# EFR32_IO.net
KiCad netlist of a schematic drawn in Altium Designer
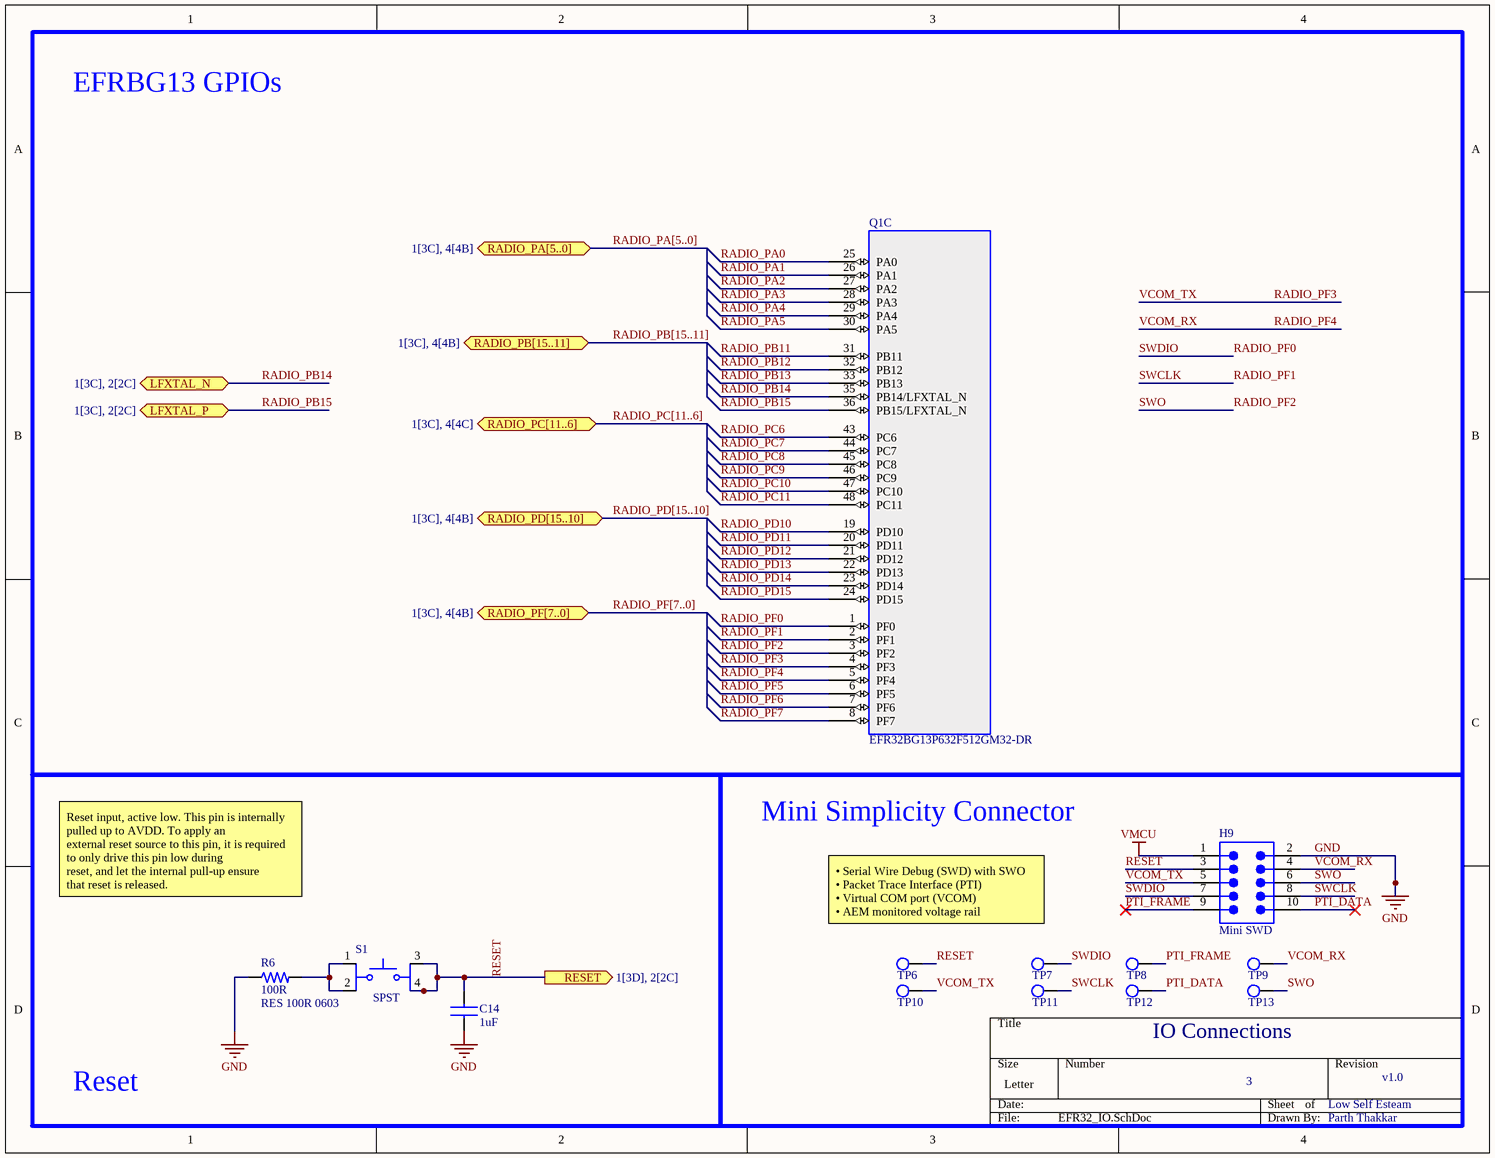
[diagram p0: EFR32_IO.SchDoc]

(export (version "E")
  (design (tool "Eeschema 10.0.6"))
  (components
    (comp (ref "C14")
      (value "1uF")
      (footprint "Capacitor 0603")
      (fields
        (field (name "MANUFACTURER") "Murata")
        (field (name "MANUFACTURER PART NUMBER") "GRM188R61A105KA61D")
        (field (name "Comment") "CAP 1uF 10V 0603")
      )
      (libsource (lib "Keyboard_parts") (part "CAP 1uF 10V 0603"))
    )
    (comp (ref "H9")
      (value "Mini SWD")
      (footprint "Mini Simplicity Connector")
      (description "Mini SWD 0.05\" Pitch Connector - 10 Pin SMT Box Header")
      (fields
        (field (name "MANUFACTURER") "Adafruit Industries")
        (field (name "MANUFACTURER PART NUMBER") "4048")
      )
      (libsource (lib "Keyboard_parts") (part "Debug Connector Mini SWD - 0.05{dblquote}"))
    )
    (comp (ref "Q1")
      (value "EFR32BG13P632F512GM32-DR")
      (footprint "EFR32BG")
      (description "BLue Gecko")
      (fields (field (name "MANUFACTURER") "Silicon Labs"))
      (libsource (lib "Keyboard_parts") (part "EFR32BG13P632F512GM32-DR"))
    )
    (comp (ref "R6")
      (value "RES 100R 0603")
      (footprint "Resistor 0603")
      (fields
        (field (name "MANUFACTURER") "Yageo")
        (field (name "MANUFACTURER PART NUMBER") "RC0603FR-07100RL")
        (field (name "TOLERANCE") "1%")
        (field (name "ALTIUM_VALUE") "100R")
      )
      (libsource (lib "Keyboard_parts") (part "RES 100R 0603"))
    )
    (comp (ref "S1")
      (value "SPST")
      (footprint "SPST")
      (fields
        (field (name "MANUFACTURER") "E-Switch")
        (field (name "MANUFACTURER PART NUMBER") "TL3301NF260QG")
      )
      (libsource (lib "Keyboard_parts") (part "SPST"))
    )
    (comp (ref "TP6")
      (value "Test point")
      (footprint "Test Point")
      (libsource (lib "Keyboard_parts") (part "Test point"))
    )
    (comp (ref "TP7")
      (value "Test point")
      (footprint "Test Point")
      (libsource (lib "Keyboard_parts") (part "Test point"))
    )
    (comp (ref "TP8")
      (value "Test point")
      (footprint "Test Point")
      (libsource (lib "Keyboard_parts") (part "Test point"))
    )
    (comp (ref "TP9")
      (value "Test point")
      (footprint "Test Point")
      (libsource (lib "Keyboard_parts") (part "Test point"))
    )
    (comp (ref "TP10")
      (value "Test point")
      (footprint "Test Point")
      (libsource (lib "Keyboard_parts") (part "Test point"))
    )
    (comp (ref "TP11")
      (value "Test point")
      (footprint "Test Point")
      (libsource (lib "Keyboard_parts") (part "Test point"))
    )
    (comp (ref "TP12")
      (value "Test point")
      (footprint "Test Point")
      (libsource (lib "Keyboard_parts") (part "Test point"))
    )
    (comp (ref "TP13")
      (value "Test point")
      (footprint "Test Point")
      (libsource (lib "Keyboard_parts") (part "Test point"))
    )
  )
  (nets
    (net (code "1") (name "/PTI_DATA") (class "Default")
      (node (ref "H9") (pin "10") (pinfunction "10_10") (pintype "passive"))
      (node (ref "TP12") (pin "1") (pinfunction "1_1") (pintype "passive"))
    )
    (net (code "2") (name "/PTI_FRAME") (class "Default")
      (node (ref "H9") (pin "9") (pinfunction "9_9") (pintype "passive"))
      (node (ref "TP8") (pin "1") (pinfunction "1_1") (pintype "passive"))
    )
    (net (code "3") (name "/RADIO_PA0") (class "Default")
      (node (ref "Q1") (pin "25") (pinfunction "PA0_25") (pintype "bidirectional"))
    )
    (net (code "4") (name "/RADIO_PA1") (class "Default")
      (node (ref "Q1") (pin "26") (pinfunction "PA1_26") (pintype "bidirectional"))
    )
    (net (code "5") (name "/RADIO_PA2") (class "Default")
      (node (ref "Q1") (pin "27") (pinfunction "PA2_27") (pintype "bidirectional"))
    )
    (net (code "6") (name "/RADIO_PA3") (class "Default")
      (node (ref "Q1") (pin "28") (pinfunction "PA3_28") (pintype "bidirectional"))
    )
    (net (code "7") (name "/RADIO_PA4") (class "Default")
      (node (ref "Q1") (pin "29") (pinfunction "PA4_29") (pintype "bidirectional"))
    )
    (net (code "8") (name "/RADIO_PA5") (class "Default")
      (node (ref "Q1") (pin "30") (pinfunction "PA5_30") (pintype "bidirectional"))
    )
    (net (code "10") (name "/RADIO_PB11") (class "Default")
      (node (ref "Q1") (pin "31") (pinfunction "PB11_31") (pintype "bidirectional"))
    )
    (net (code "11") (name "/RADIO_PB12") (class "Default")
      (node (ref "Q1") (pin "32") (pinfunction "PB12_32") (pintype "bidirectional"))
    )
    (net (code "12") (name "/RADIO_PB13") (class "Default")
      (node (ref "Q1") (pin "33") (pinfunction "PB13_33") (pintype "bidirectional"))
    )
    (net (code "13") (name "/RADIO_PB14") (class "Default")
      (node (ref "Q1") (pin "35") (pinfunction "PB14/LFXTAL_N_35") (pintype "bidirectional"))
    )
    (net (code "14") (name "/RADIO_PB15") (class "Default")
      (node (ref "Q1") (pin "36") (pinfunction "PB15/LFXTAL_N_36") (pintype "bidirectional"))
    )
    (net (code "16") (name "/RADIO_PC6") (class "Default")
      (node (ref "Q1") (pin "43") (pinfunction "PC6_43") (pintype "bidirectional"))
    )
    (net (code "17") (name "/RADIO_PC7") (class "Default")
      (node (ref "Q1") (pin "44") (pinfunction "PC7_44") (pintype "bidirectional"))
    )
    (net (code "18") (name "/RADIO_PC8") (class "Default")
      (node (ref "Q1") (pin "45") (pinfunction "PC8_45") (pintype "bidirectional"))
    )
    (net (code "19") (name "/RADIO_PC9") (class "Default")
      (node (ref "Q1") (pin "46") (pinfunction "PC9_46") (pintype "bidirectional"))
    )
    (net (code "20") (name "/RADIO_PC10") (class "Default")
      (node (ref "Q1") (pin "47") (pinfunction "PC10_47") (pintype "bidirectional"))
    )
    (net (code "21") (name "/RADIO_PC11") (class "Default")
      (node (ref "Q1") (pin "48") (pinfunction "PC11_48") (pintype "bidirectional"))
    )
    (net (code "23") (name "/RADIO_PD10") (class "Default")
      (node (ref "Q1") (pin "19") (pinfunction "PD10_19") (pintype "bidirectional"))
    )
    (net (code "24") (name "/RADIO_PD11") (class "Default")
      (node (ref "Q1") (pin "20") (pinfunction "PD11_20") (pintype "bidirectional"))
    )
    (net (code "25") (name "/RADIO_PD12") (class "Default")
      (node (ref "Q1") (pin "21") (pinfunction "PD12_21") (pintype "bidirectional"))
    )
    (net (code "26") (name "/RADIO_PD13") (class "Default")
      (node (ref "Q1") (pin "22") (pinfunction "PD13_22") (pintype "bidirectional"))
    )
    (net (code "27") (name "/RADIO_PD14") (class "Default")
      (node (ref "Q1") (pin "23") (pinfunction "PD14_23") (pintype "bidirectional"))
    )
    (net (code "28") (name "/RADIO_PD15") (class "Default")
      (node (ref "Q1") (pin "24") (pinfunction "PD15_24") (pintype "bidirectional"))
    )
    (net (code "30") (name "/RADIO_PF0") (class "Default")
      (node (ref "H9") (pin "7") (pinfunction "7_7") (pintype "passive"))
      (node (ref "Q1") (pin "1") (pinfunction "PF0_1") (pintype "bidirectional"))
      (node (ref "TP7") (pin "1") (pinfunction "1_1") (pintype "passive"))
    )
    (net (code "31") (name "/RADIO_PF1") (class "Default")
      (node (ref "H9") (pin "8") (pinfunction "8_8") (pintype "passive"))
      (node (ref "Q1") (pin "2") (pinfunction "PF1_2") (pintype "bidirectional"))
      (node (ref "TP11") (pin "1") (pinfunction "1_1") (pintype "passive"))
    )
    (net (code "32") (name "/RADIO_PF2") (class "Default")
      (node (ref "H9") (pin "6") (pinfunction "6_6") (pintype "passive"))
      (node (ref "Q1") (pin "3") (pinfunction "PF2_3") (pintype "bidirectional"))
      (node (ref "TP13") (pin "1") (pinfunction "1_1") (pintype "passive"))
    )
    (net (code "33") (name "/RADIO_PF3") (class "Default")
      (node (ref "H9") (pin "5") (pinfunction "5_5") (pintype "passive"))
      (node (ref "Q1") (pin "4") (pinfunction "PF3_4") (pintype "bidirectional"))
      (node (ref "TP10") (pin "1") (pinfunction "1_1") (pintype "passive"))
    )
    (net (code "34") (name "/RADIO_PF4") (class "Default")
      (node (ref "H9") (pin "4") (pinfunction "4_4") (pintype "passive"))
      (node (ref "Q1") (pin "5") (pinfunction "PF4_5") (pintype "bidirectional"))
      (node (ref "TP9") (pin "1") (pinfunction "1_1") (pintype "passive"))
    )
    (net (code "35") (name "/RADIO_PF5") (class "Default")
      (node (ref "Q1") (pin "6") (pinfunction "PF5_6") (pintype "bidirectional"))
    )
    (net (code "36") (name "/RADIO_PF6") (class "Default")
      (node (ref "Q1") (pin "7") (pinfunction "PF6_7") (pintype "bidirectional"))
    )
    (net (code "37") (name "/RADIO_PF7") (class "Default")
      (node (ref "Q1") (pin "8") (pinfunction "PF7_8") (pintype "bidirectional"))
    )
    (net (code "39") (name "/RESET") (class "Default")
      (node (ref "C14") (pin "1") (pinfunction "1_1") (pintype "passive"))
      (node (ref "H9") (pin "3") (pinfunction "3_3") (pintype "passive"))
      (node (ref "S1") (pin "3") (pinfunction "3_3") (pintype "passive"))
      (node (ref "S1") (pin "4") (pinfunction "4_4") (pintype "passive"))
      (node (ref "TP6") (pin "1") (pinfunction "1_1") (pintype "passive"))
    )
    (net (code "40") (name "GND") (class "Default")
      (node (ref "C14") (pin "2") (pinfunction "2_2") (pintype "passive"))
      (node (ref "H9") (pin "2") (pinfunction "2_2") (pintype "passive"))
      (node (ref "R6") (pin "1") (pinfunction "1_1") (pintype "passive"))
    )
    (net (code "41") (name "Net-(R6-Pad2)") (class "Default")
      (node (ref "R6") (pin "2") (pinfunction "2_2") (pintype "passive"))
      (node (ref "S1") (pin "1") (pinfunction "1_1") (pintype "passive"))
      (node (ref "S1") (pin "2") (pinfunction "2_2") (pintype "passive"))
    )
    (net (code "42") (name "VMCU") (class "Default")
      (node (ref "H9") (pin "1") (pinfunction "1_1") (pintype "passive"))
    )
  )
)
